# TinkerKit-concept.net
KiCad netlist of a schematic drawn in EAGLE
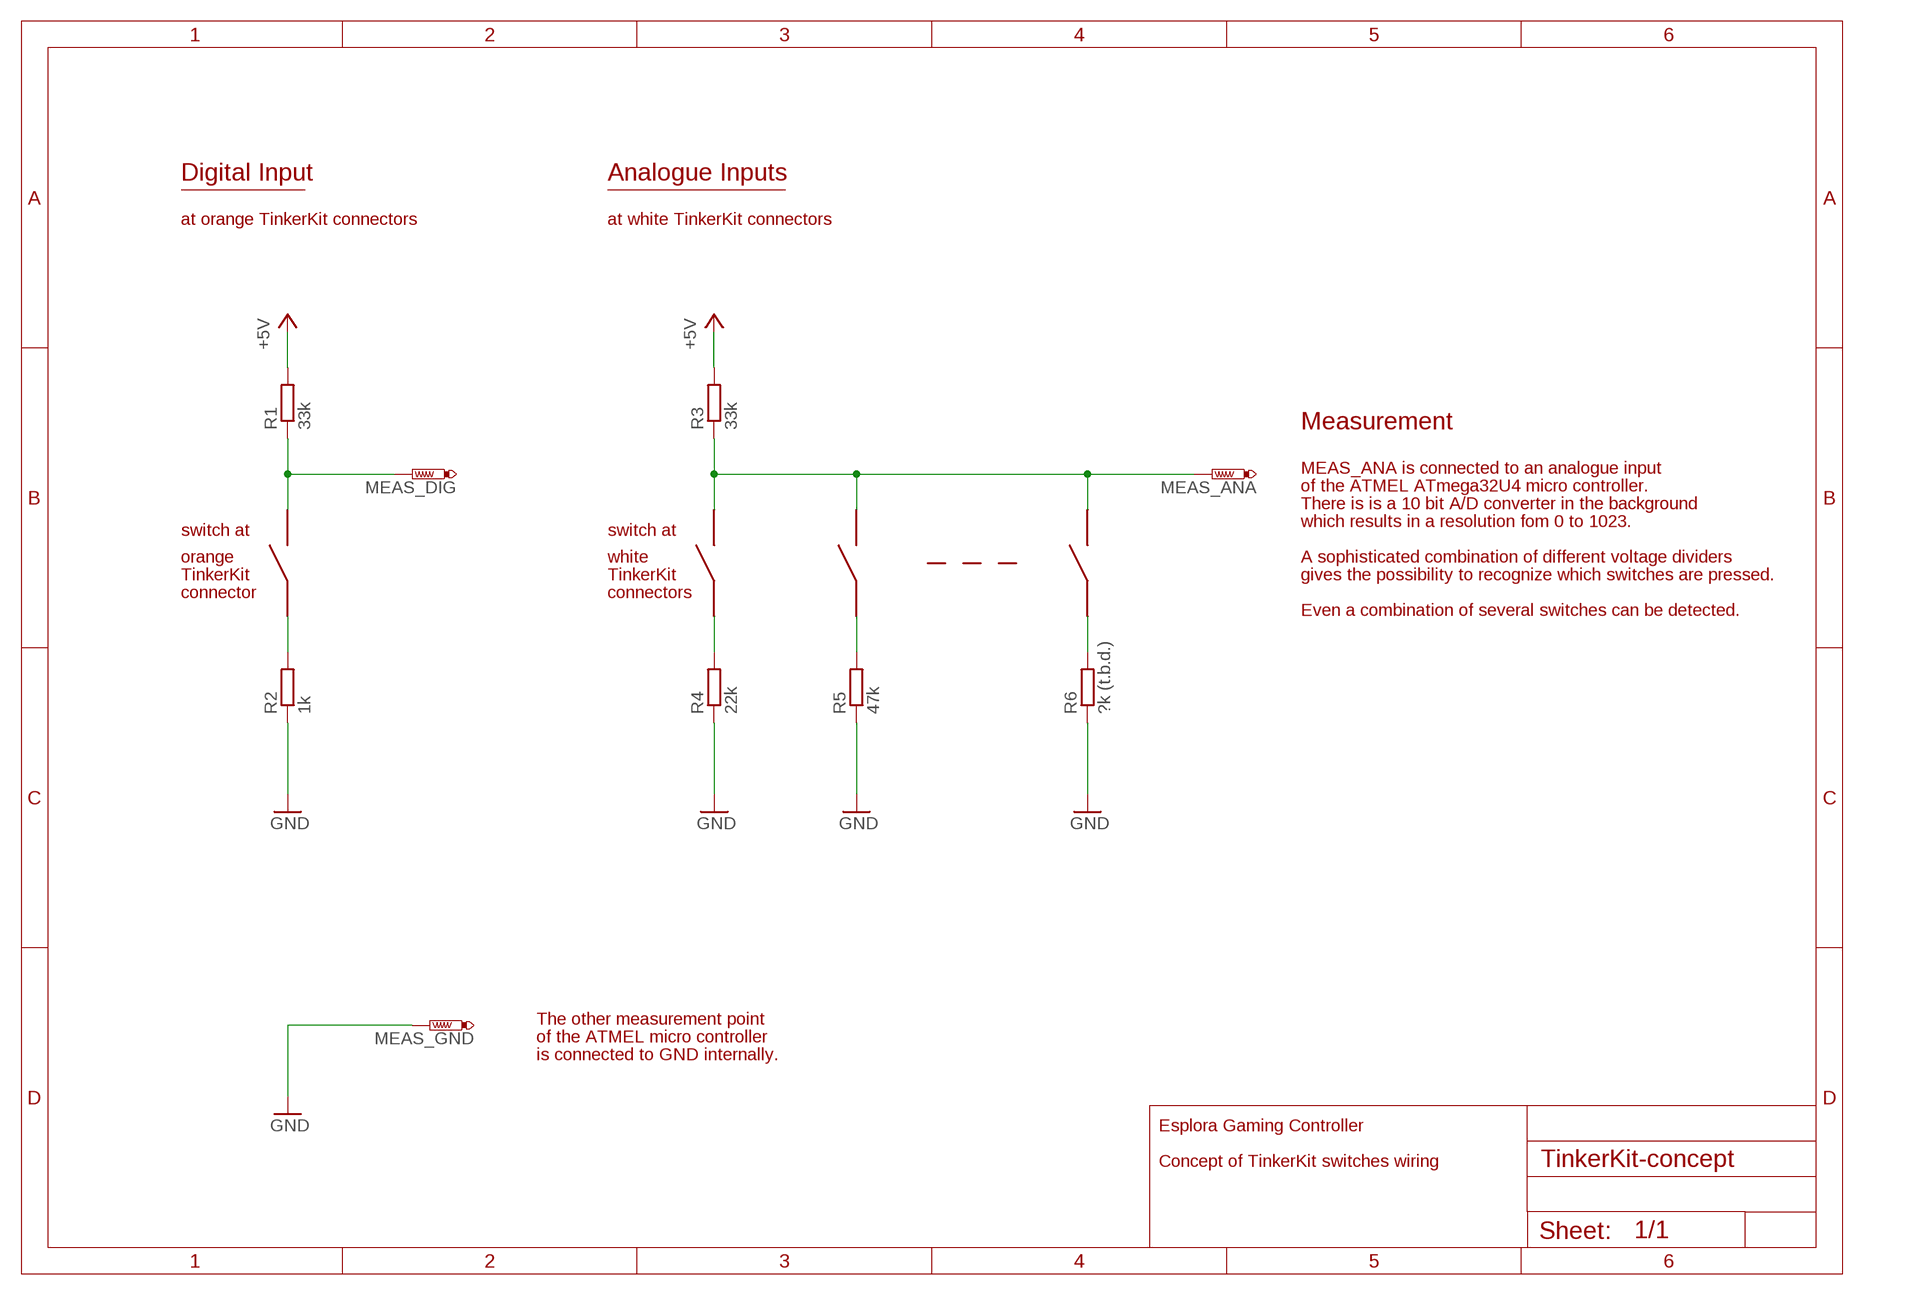
[diagram p0: schematic, sheet 1]

(export (version "E")
  (design (tool "Eeschema 10.0.6"))
  (components
    (comp (ref "MEAS_ANA")
      (value "PTR1B1,27")
      (footprint "eagle-import:B1,27")
      (libsource (lib "eagle-import") (part "PTR1B1,27"))
    )
    (comp (ref "MEAS_DIG")
      (value "PTR1B1,27")
      (footprint "eagle-import:B1,27")
      (libsource (lib "eagle-import") (part "PTR1B1,27"))
    )
    (comp (ref "MEAS_GND")
      (value "PTR1B1,27")
      (footprint "eagle-import:B1,27")
      (libsource (lib "eagle-import") (part "PTR1B1,27"))
    )
    (comp (ref "R1")
      (value "33k")
      (footprint "eagle-import:M1206")
      (libsource (lib "eagle-import") (part "R-EU_M1206"))
    )
    (comp (ref "R2")
      (value "1k")
      (footprint "eagle-import:M1206")
      (libsource (lib "eagle-import") (part "R-EU_M1206"))
    )
    (comp (ref "R3")
      (value "33k")
      (footprint "eagle-import:M1206")
      (libsource (lib "eagle-import") (part "R-EU_M1206"))
    )
    (comp (ref "R4")
      (value "22k")
      (footprint "eagle-import:M1206")
      (libsource (lib "eagle-import") (part "R-EU_M1206"))
    )
    (comp (ref "R5")
      (value "47k")
      (footprint "eagle-import:M1206")
      (libsource (lib "eagle-import") (part "R-EU_M1206"))
    )
    (comp (ref "R6")
      (value "?k (t.b.d.)")
      (footprint "eagle-import:M1206")
      (libsource (lib "eagle-import") (part "R-EU_M1206"))
    )
  )
  (nets
    (net (code "1") (name "+5V") (class "Default")
      (node (ref "R1") (pin "2") (pinfunction "2_2") (pintype "passive"))
      (node (ref "R3") (pin "2") (pinfunction "2_2") (pintype "passive"))
    )
    (net (code "2") (name "GND") (class "Default")
      (node (ref "MEAS_GND") (pin "TP") (pinfunction "TP_TP") (pintype "input"))
      (node (ref "R2") (pin "1") (pinfunction "1_1") (pintype "passive"))
      (node (ref "R4") (pin "1") (pinfunction "1_1") (pintype "passive"))
      (node (ref "R5") (pin "1") (pinfunction "1_1") (pintype "passive"))
      (node (ref "R6") (pin "1") (pinfunction "1_1") (pintype "passive"))
    )
    (net (code "3") (name "Net-(MEAS_ANA-PadTP)") (class "Default")
      (node (ref "MEAS_ANA") (pin "TP") (pinfunction "TP_TP") (pintype "input"))
      (node (ref "R3") (pin "1") (pinfunction "1_1") (pintype "passive"))
    )
    (net (code "4") (name "Net-(MEAS_DIG-PadTP)") (class "Default")
      (node (ref "MEAS_DIG") (pin "TP") (pinfunction "TP_TP") (pintype "input"))
      (node (ref "R1") (pin "1") (pinfunction "1_1") (pintype "passive"))
    )
    (net (code "5") (name "unconnected-(R2-Pad2)") (class "Default")
      (node (ref "R2") (pin "2") (pinfunction "2_2") (pintype "passive"))
    )
    (net (code "6") (name "unconnected-(R4-Pad2)") (class "Default")
      (node (ref "R4") (pin "2") (pinfunction "2_2") (pintype "passive"))
    )
    (net (code "7") (name "unconnected-(R5-Pad2)") (class "Default")
      (node (ref "R5") (pin "2") (pinfunction "2_2") (pintype "passive"))
    )
    (net (code "8") (name "unconnected-(R6-Pad2)") (class "Default")
      (node (ref "R6") (pin "2") (pinfunction "2_2") (pintype "passive"))
    )
  )
)
